# ADS1298_V1.net
KiCad netlist of a schematic drawn in EAGLE
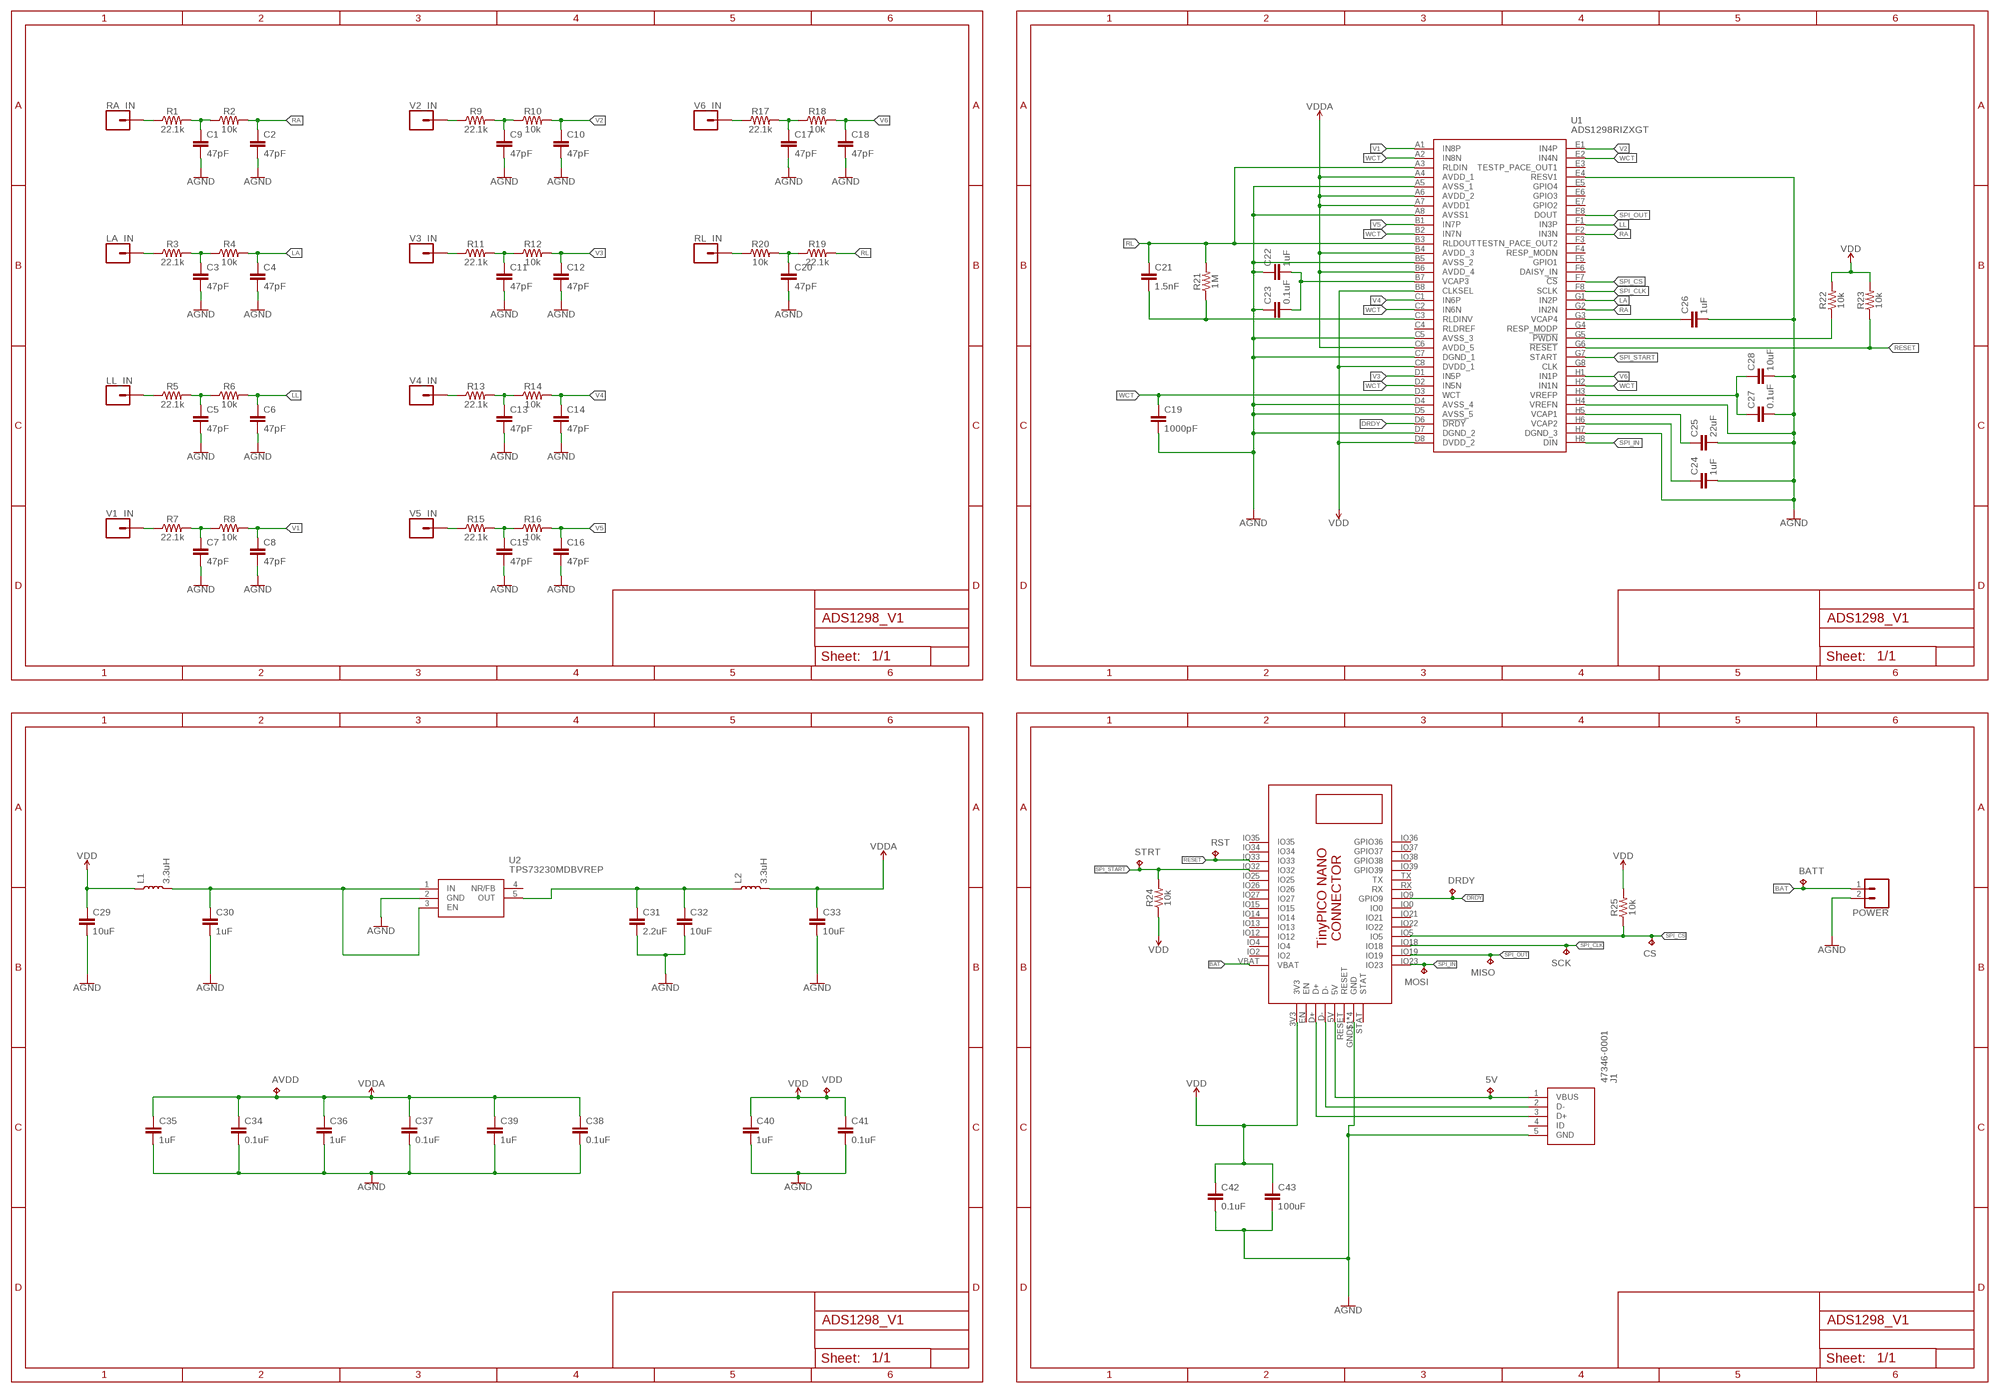
[diagram p0: schematic, sheet 1]

(export (version "E")
  (design (tool "Eeschema 10.0.6"))
  (components
    (comp (ref "5V")
      (value "TPB1,27")
      (footprint "eagle-import:B1,27")
      (libsource (lib "eagle-import") (part "TPB1,27"))
    )
    (comp (ref "AVDD")
      (value "TPB1,27")
      (footprint "eagle-import:B1,27")
      (libsource (lib "eagle-import") (part "TPB1,27"))
    )
    (comp (ref "BATT")
      (value "TPB1,27")
      (footprint "eagle-import:B1,27")
      (libsource (lib "eagle-import") (part "TPB1,27"))
    )
    (comp (ref "C1")
      (value "47pF")
      (footprint "eagle-import:0603")
      (libsource (lib "eagle-import") (part "CAP-0603"))
    )
    (comp (ref "C2")
      (value "47pF")
      (footprint "eagle-import:0603")
      (libsource (lib "eagle-import") (part "CAP-0603"))
    )
    (comp (ref "C3")
      (value "47pF")
      (footprint "eagle-import:0603")
      (libsource (lib "eagle-import") (part "CAP-0603"))
    )
    (comp (ref "C4")
      (value "47pF")
      (footprint "eagle-import:0603")
      (libsource (lib "eagle-import") (part "CAP-0603"))
    )
    (comp (ref "C5")
      (value "47pF")
      (footprint "eagle-import:0603")
      (libsource (lib "eagle-import") (part "CAP-0603"))
    )
    (comp (ref "C6")
      (value "47pF")
      (footprint "eagle-import:0603")
      (libsource (lib "eagle-import") (part "CAP-0603"))
    )
    (comp (ref "C7")
      (value "47pF")
      (footprint "eagle-import:0603")
      (libsource (lib "eagle-import") (part "CAP-0603"))
    )
    (comp (ref "C8")
      (value "47pF")
      (footprint "eagle-import:0603")
      (libsource (lib "eagle-import") (part "CAP-0603"))
    )
    (comp (ref "C9")
      (value "47pF")
      (footprint "eagle-import:0603")
      (libsource (lib "eagle-import") (part "CAP-0603"))
    )
    (comp (ref "C10")
      (value "47pF")
      (footprint "eagle-import:0603")
      (libsource (lib "eagle-import") (part "CAP-0603"))
    )
    (comp (ref "C11")
      (value "47pF")
      (footprint "eagle-import:0603")
      (libsource (lib "eagle-import") (part "CAP-0603"))
    )
    (comp (ref "C12")
      (value "47pF")
      (footprint "eagle-import:0603")
      (libsource (lib "eagle-import") (part "CAP-0603"))
    )
    (comp (ref "C13")
      (value "47pF")
      (footprint "eagle-import:0603")
      (libsource (lib "eagle-import") (part "CAP-0603"))
    )
    (comp (ref "C14")
      (value "47pF")
      (footprint "eagle-import:0603")
      (libsource (lib "eagle-import") (part "CAP-0603"))
    )
    (comp (ref "C15")
      (value "47pF")
      (footprint "eagle-import:0603")
      (libsource (lib "eagle-import") (part "CAP-0603"))
    )
    (comp (ref "C16")
      (value "47pF")
      (footprint "eagle-import:0603")
      (libsource (lib "eagle-import") (part "CAP-0603"))
    )
    (comp (ref "C17")
      (value "47pF")
      (footprint "eagle-import:0603")
      (libsource (lib "eagle-import") (part "CAP-0603"))
    )
    (comp (ref "C18")
      (value "47pF")
      (footprint "eagle-import:0603")
      (libsource (lib "eagle-import") (part "CAP-0603"))
    )
    (comp (ref "C19")
      (value "1000pF")
      (footprint "eagle-import:0603")
      (libsource (lib "eagle-import") (part "CAP-0603"))
    )
    (comp (ref "C20")
      (value "47pF")
      (footprint "eagle-import:0603")
      (libsource (lib "eagle-import") (part "CAP-0603"))
    )
    (comp (ref "C21")
      (value "1.5nF")
      (footprint "eagle-import:0603")
      (libsource (lib "eagle-import") (part "CAP-0603"))
    )
    (comp (ref "C22")
      (value "1uF")
      (footprint "eagle-import:0603")
      (libsource (lib "eagle-import") (part "CAP-0603"))
    )
    (comp (ref "C23")
      (value "0.1uF")
      (footprint "eagle-import:0603")
      (libsource (lib "eagle-import") (part "CAP-0603"))
    )
    (comp (ref "C24")
      (value "1uF")
      (footprint "eagle-import:0603")
      (libsource (lib "eagle-import") (part "CAP-0603"))
    )
    (comp (ref "C25")
      (value "22uF")
      (footprint "eagle-import:0805")
      (libsource (lib "eagle-import") (part "CAP-0805"))
    )
    (comp (ref "C26")
      (value "1uF")
      (footprint "eagle-import:0603")
      (libsource (lib "eagle-import") (part "CAP-0603"))
    )
    (comp (ref "C27")
      (value "0.1uF")
      (footprint "eagle-import:0603")
      (libsource (lib "eagle-import") (part "CAP-0603"))
    )
    (comp (ref "C28")
      (value "10uF")
      (footprint "eagle-import:0805")
      (libsource (lib "eagle-import") (part "CAP-0805"))
    )
    (comp (ref "C29")
      (value "10uF")
      (footprint "eagle-import:0805")
      (libsource (lib "eagle-import") (part "CAP-0805"))
    )
    (comp (ref "C30")
      (value "1uF")
      (footprint "eagle-import:0603")
      (libsource (lib "eagle-import") (part "CAP-0603"))
    )
    (comp (ref "C31")
      (value "2.2uF")
      (footprint "eagle-import:0603")
      (libsource (lib "eagle-import") (part "CAP-0603"))
    )
    (comp (ref "C32")
      (value "10uF")
      (footprint "eagle-import:0805")
      (libsource (lib "eagle-import") (part "CAP-0805"))
    )
    (comp (ref "C33")
      (value "10uF")
      (footprint "eagle-import:0805")
      (libsource (lib "eagle-import") (part "CAP-0805"))
    )
    (comp (ref "C34")
      (value "0.1uF")
      (footprint "eagle-import:0603")
      (libsource (lib "eagle-import") (part "CAP-0603"))
    )
    (comp (ref "C35")
      (value "1uF")
      (footprint "eagle-import:0603")
      (libsource (lib "eagle-import") (part "CAP-0603"))
    )
    (comp (ref "C36")
      (value "1uF")
      (footprint "eagle-import:0603")
      (libsource (lib "eagle-import") (part "CAP-0603"))
    )
    (comp (ref "C37")
      (value "0.1uF")
      (footprint "eagle-import:0603")
      (libsource (lib "eagle-import") (part "CAP-0603"))
    )
    (comp (ref "C38")
      (value "0.1uF")
      (footprint "eagle-import:0603")
      (libsource (lib "eagle-import") (part "CAP-0603"))
    )
    (comp (ref "C39")
      (value "1uF")
      (footprint "eagle-import:0603")
      (libsource (lib "eagle-import") (part "CAP-0603"))
    )
    (comp (ref "C40")
      (value "1uF")
      (footprint "eagle-import:0603")
      (libsource (lib "eagle-import") (part "CAP-0603"))
    )
    (comp (ref "C41")
      (value "0.1uF")
      (footprint "eagle-import:0603")
      (libsource (lib "eagle-import") (part "CAP-0603"))
    )
    (comp (ref "C42")
      (value "0.1uF")
      (footprint "eagle-import:0603")
      (libsource (lib "eagle-import") (part "CAP-0603"))
    )
    (comp (ref "C43")
      (value "100uF")
      (footprint "eagle-import:0805")
      (libsource (lib "eagle-import") (part "CAP-0805"))
    )
    (comp (ref "CS")
      (value "TPB1,27")
      (footprint "eagle-import:B1,27")
      (libsource (lib "eagle-import") (part "TPB1,27"))
    )
    (comp (ref "DRDY")
      (value "TPB1,27")
      (footprint "eagle-import:B1,27")
      (libsource (lib "eagle-import") (part "TPB1,27"))
    )
    (comp (ref "J1")
      (value "47346-0001")
      (footprint "eagle-import:47346-0001")
      (fields (field (name "MOUSER_PART_NUMBER") "538-47346-0001"))
      (libsource (lib "eagle-import") (part "47346-0001"))
    )
    (comp (ref "L1")
      (value "3.3uH")
      (footprint "eagle-import:0805")
      (libsource (lib "eagle-import") (part "INDUCTOR-0805-3.3UH"))
    )
    (comp (ref "L2")
      (value "3.3uH")
      (footprint "eagle-import:0805")
      (libsource (lib "eagle-import") (part "INDUCTOR-0805-3.3UH"))
    )
    (comp (ref "LA_IN")
      (value "CONN_01")
      (footprint "eagle-import:1X01")
      (libsource (lib "eagle-import") (part "CONN_01"))
    )
    (comp (ref "LL_IN")
      (value "CONN_01")
      (footprint "eagle-import:1X01")
      (libsource (lib "eagle-import") (part "CONN_01"))
    )
    (comp (ref "MISO")
      (value "TPB1,27")
      (footprint "eagle-import:B1,27")
      (libsource (lib "eagle-import") (part "TPB1,27"))
    )
    (comp (ref "MOSI")
      (value "TPB1,27")
      (footprint "eagle-import:B1,27")
      (libsource (lib "eagle-import") (part "TPB1,27"))
    )
    (comp (ref "POWER")
      (value "CONN_02")
      (footprint "eagle-import:1X02")
      (libsource (lib "eagle-import") (part "CONN_02"))
    )
    (comp (ref "R1")
      (value "22.1k")
      (footprint "eagle-import:0603")
      (libsource (lib "eagle-import") (part "RESISTOR0603"))
    )
    (comp (ref "R2")
      (value "10k")
      (footprint "eagle-import:0603")
      (libsource (lib "eagle-import") (part "RESISTOR0603"))
    )
    (comp (ref "R3")
      (value "22.1k")
      (footprint "eagle-import:0603")
      (libsource (lib "eagle-import") (part "RESISTOR0603"))
    )
    (comp (ref "R4")
      (value "10k")
      (footprint "eagle-import:0603")
      (libsource (lib "eagle-import") (part "RESISTOR0603"))
    )
    (comp (ref "R5")
      (value "22.1k")
      (footprint "eagle-import:0603")
      (libsource (lib "eagle-import") (part "RESISTOR0603"))
    )
    (comp (ref "R6")
      (value "10k")
      (footprint "eagle-import:0603")
      (libsource (lib "eagle-import") (part "RESISTOR0603"))
    )
    (comp (ref "R7")
      (value "22.1k")
      (footprint "eagle-import:0603")
      (libsource (lib "eagle-import") (part "RESISTOR0603"))
    )
    (comp (ref "R8")
      (value "10k")
      (footprint "eagle-import:0603")
      (libsource (lib "eagle-import") (part "RESISTOR0603"))
    )
    (comp (ref "R9")
      (value "22.1k")
      (footprint "eagle-import:0603")
      (libsource (lib "eagle-import") (part "RESISTOR0603"))
    )
    (comp (ref "R10")
      (value "10k")
      (footprint "eagle-import:0603")
      (libsource (lib "eagle-import") (part "RESISTOR0603"))
    )
    (comp (ref "R11")
      (value "22.1k")
      (footprint "eagle-import:0603")
      (libsource (lib "eagle-import") (part "RESISTOR0603"))
    )
    (comp (ref "R12")
      (value "10k")
      (footprint "eagle-import:0603")
      (libsource (lib "eagle-import") (part "RESISTOR0603"))
    )
    (comp (ref "R13")
      (value "22.1k")
      (footprint "eagle-import:0603")
      (libsource (lib "eagle-import") (part "RESISTOR0603"))
    )
    (comp (ref "R14")
      (value "10k")
      (footprint "eagle-import:0603")
      (libsource (lib "eagle-import") (part "RESISTOR0603"))
    )
    (comp (ref "R15")
      (value "22.1k")
      (footprint "eagle-import:0603")
      (libsource (lib "eagle-import") (part "RESISTOR0603"))
    )
    (comp (ref "R16")
      (value "10k")
      (footprint "eagle-import:0603")
      (libsource (lib "eagle-import") (part "RESISTOR0603"))
    )
    (comp (ref "R17")
      (value "22.1k")
      (footprint "eagle-import:0603")
      (libsource (lib "eagle-import") (part "RESISTOR0603"))
    )
    (comp (ref "R18")
      (value "10k")
      (footprint "eagle-import:0603")
      (libsource (lib "eagle-import") (part "RESISTOR0603"))
    )
    (comp (ref "R19")
      (value "22.1k")
      (footprint "eagle-import:0603")
      (libsource (lib "eagle-import") (part "RESISTOR0603"))
    )
    (comp (ref "R20")
      (value "10k")
      (footprint "eagle-import:0603")
      (libsource (lib "eagle-import") (part "RESISTOR0603"))
    )
    (comp (ref "R21")
      (value "1M")
      (footprint "eagle-import:0603")
      (libsource (lib "eagle-import") (part "RESISTOR0603"))
    )
    (comp (ref "R22")
      (value "10k")
      (footprint "eagle-import:0603")
      (libsource (lib "eagle-import") (part "RESISTOR0603"))
    )
    (comp (ref "R23")
      (value "10k")
      (footprint "eagle-import:0603")
      (libsource (lib "eagle-import") (part "RESISTOR0603"))
    )
    (comp (ref "R24")
      (value "10k")
      (footprint "eagle-import:0603")
      (libsource (lib "eagle-import") (part "RESISTOR0603"))
    )
    (comp (ref "R25")
      (value "10k")
      (footprint "eagle-import:0603")
      (libsource (lib "eagle-import") (part "RESISTOR0603"))
    )
    (comp (ref "RA_IN")
      (value "CONN_01")
      (footprint "eagle-import:1X01")
      (libsource (lib "eagle-import") (part "CONN_01"))
    )
    (comp (ref "RL_IN")
      (value "CONN_01")
      (footprint "eagle-import:1X01")
      (libsource (lib "eagle-import") (part "CONN_01"))
    )
    (comp (ref "RST")
      (value "TPB1,27")
      (footprint "eagle-import:B1,27")
      (libsource (lib "eagle-import") (part "TPB1,27"))
    )
    (comp (ref "SCK")
      (value "TPB1,27")
      (footprint "eagle-import:B1,27")
      (libsource (lib "eagle-import") (part "TPB1,27"))
    )
    (comp (ref "STRT")
      (value "TPB1,27")
      (footprint "eagle-import:B1,27")
      (libsource (lib "eagle-import") (part "TPB1,27"))
    )
    (comp (ref "U1")
      (value "ADS1298RIZXGT")
      (footprint "eagle-import:BGA64C80P8X8_800X800X145")
      (fields (field (name "MOUSER_PART_NUMBER") "595-ADS1298RIZXGT"))
      (libsource (lib "eagle-import") (part "ADS1298RIZXGT"))
    )
    (comp (ref "U2")
      (value "TPS73230MDBVREP")
      (footprint "eagle-import:SOT95P280X145-5N")
      (fields (field (name "MOUSER_PART_NUMBER") "595-TPS73230MDBVREP"))
      (libsource (lib "eagle-import") (part "TPS73230MDBVREP"))
    )
    (comp (ref "U3")
      (value "TINYPICO-NANO-CONNECTOR")
      (footprint "eagle-import:TINYPICO-NANO-CONNECTOR")
      (libsource (lib "eagle-import") (part "TINYPICO-NANO-CONNECTOR"))
    )
    (comp (ref "V1_IN")
      (value "CONN_01")
      (footprint "eagle-import:1X01")
      (libsource (lib "eagle-import") (part "CONN_01"))
    )
    (comp (ref "V2_IN")
      (value "CONN_01")
      (footprint "eagle-import:1X01")
      (libsource (lib "eagle-import") (part "CONN_01"))
    )
    (comp (ref "V3_IN")
      (value "CONN_01")
      (footprint "eagle-import:1X01")
      (libsource (lib "eagle-import") (part "CONN_01"))
    )
    (comp (ref "V4_IN")
      (value "CONN_01")
      (footprint "eagle-import:1X01")
      (libsource (lib "eagle-import") (part "CONN_01"))
    )
    (comp (ref "V5_IN")
      (value "CONN_01")
      (footprint "eagle-import:1X01")
      (libsource (lib "eagle-import") (part "CONN_01"))
    )
    (comp (ref "V6_IN")
      (value "CONN_01")
      (footprint "eagle-import:1X01")
      (libsource (lib "eagle-import") (part "CONN_01"))
    )
    (comp (ref "VDD")
      (value "TPB1,27")
      (footprint "eagle-import:B1,27")
      (libsource (lib "eagle-import") (part "TPB1,27"))
    )
  )
  (nets
    (net (code "1") (name "AGND") (class "Default")
      (node (ref "C1") (pin "2") (pinfunction "2_2") (pintype "passive"))
      (node (ref "C10") (pin "2") (pinfunction "2_2") (pintype "passive"))
      (node (ref "C11") (pin "2") (pinfunction "2_2") (pintype "passive"))
      (node (ref "C12") (pin "2") (pinfunction "2_2") (pintype "passive"))
      (node (ref "C13") (pin "2") (pinfunction "2_2") (pintype "passive"))
      (node (ref "C14") (pin "2") (pinfunction "2_2") (pintype "passive"))
      (node (ref "C15") (pin "2") (pinfunction "2_2") (pintype "passive"))
      (node (ref "C16") (pin "2") (pinfunction "2_2") (pintype "passive"))
      (node (ref "C17") (pin "2") (pinfunction "2_2") (pintype "passive"))
      (node (ref "C18") (pin "2") (pinfunction "2_2") (pintype "passive"))
      (node (ref "C19") (pin "2") (pinfunction "2_2") (pintype "passive"))
      (node (ref "C2") (pin "2") (pinfunction "2_2") (pintype "passive"))
      (node (ref "C20") (pin "2") (pinfunction "2_2") (pintype "passive"))
      (node (ref "C22") (pin "1") (pinfunction "1_1") (pintype "passive"))
      (node (ref "C23") (pin "1") (pinfunction "1_1") (pintype "passive"))
      (node (ref "C24") (pin "2") (pinfunction "2_2") (pintype "passive"))
      (node (ref "C25") (pin "2") (pinfunction "2_2") (pintype "passive"))
      (node (ref "C26") (pin "2") (pinfunction "2_2") (pintype "passive"))
      (node (ref "C27") (pin "2") (pinfunction "2_2") (pintype "passive"))
      (node (ref "C28") (pin "2") (pinfunction "2_2") (pintype "passive"))
      (node (ref "C29") (pin "2") (pinfunction "2_2") (pintype "passive"))
      (node (ref "C3") (pin "2") (pinfunction "2_2") (pintype "passive"))
      (node (ref "C30") (pin "2") (pinfunction "2_2") (pintype "passive"))
      (node (ref "C31") (pin "2") (pinfunction "2_2") (pintype "passive"))
      (node (ref "C32") (pin "2") (pinfunction "2_2") (pintype "passive"))
      (node (ref "C33") (pin "2") (pinfunction "2_2") (pintype "passive"))
      (node (ref "C34") (pin "2") (pinfunction "2_2") (pintype "passive"))
      (node (ref "C35") (pin "2") (pinfunction "2_2") (pintype "passive"))
      (node (ref "C36") (pin "2") (pinfunction "2_2") (pintype "passive"))
      (node (ref "C37") (pin "2") (pinfunction "2_2") (pintype "passive"))
      (node (ref "C38") (pin "2") (pinfunction "2_2") (pintype "passive"))
      (node (ref "C39") (pin "2") (pinfunction "2_2") (pintype "passive"))
      (node (ref "C4") (pin "2") (pinfunction "2_2") (pintype "passive"))
      (node (ref "C40") (pin "2") (pinfunction "2_2") (pintype "passive"))
      (node (ref "C41") (pin "2") (pinfunction "2_2") (pintype "passive"))
      (node (ref "C42") (pin "2") (pinfunction "2_2") (pintype "passive"))
      (node (ref "C43") (pin "2") (pinfunction "2_2") (pintype "passive"))
      (node (ref "C5") (pin "2") (pinfunction "2_2") (pintype "passive"))
      (node (ref "C6") (pin "2") (pinfunction "2_2") (pintype "passive"))
      (node (ref "C7") (pin "2") (pinfunction "2_2") (pintype "passive"))
      (node (ref "C8") (pin "2") (pinfunction "2_2") (pintype "passive"))
      (node (ref "C9") (pin "2") (pinfunction "2_2") (pintype "passive"))
      (node (ref "J1") (pin "5") (pinfunction "GND_5") (pintype "bidirectional"))
      (node (ref "POWER") (pin "2") (pinfunction "2_2") (pintype "passive"))
      (node (ref "U1") (pin "A5") (pinfunction "AVSS_1_A5") (pintype "bidirectional"))
      (node (ref "U1") (pin "A8") (pinfunction "AVSS1_A8") (pintype "bidirectional"))
      (node (ref "U1") (pin "B5") (pinfunction "AVSS_2_B5") (pintype "bidirectional"))
      (node (ref "U1") (pin "C5") (pinfunction "AVSS_3_C5") (pintype "bidirectional"))
      (node (ref "U1") (pin "C7") (pinfunction "DGND_1_C7") (pintype "bidirectional"))
      (node (ref "U1") (pin "D4") (pinfunction "AVSS_4_D4") (pintype "bidirectional"))
      (node (ref "U1") (pin "D5") (pinfunction "AVSS_5_D5") (pintype "bidirectional"))
      (node (ref "U1") (pin "D7") (pinfunction "DGND_2_D7") (pintype "bidirectional"))
      (node (ref "U1") (pin "E4") (pinfunction "RESV1_E4") (pintype "bidirectional"))
      (node (ref "U1") (pin "H4") (pinfunction "VREFN_H4") (pintype "bidirectional"))
      (node (ref "U1") (pin "H7") (pinfunction "DGND_3_H7") (pintype "bidirectional"))
      (node (ref "U2") (pin "2") (pinfunction "GND_2") (pintype "bidirectional"))
      (node (ref "U3") (pin "GND$1") (pinfunction "GND_GND$1") (pintype "power_in"))
      (node (ref "U3") (pin "GND$2") (pinfunction "GND_GND$2") (pintype "power_in"))
      (node (ref "U3") (pin "GND$3") (pinfunction "GND_GND$3") (pintype "power_in"))
      (node (ref "U3") (pin "GND$4") (pinfunction "GND_GND$4") (pintype "power_in"))
    )
    (net (code "2") (name "BAT") (class "Default")
      (node (ref "BATT") (pin "TP") (pinfunction "TP_TP") (pintype "input"))
      (node (ref "POWER") (pin "1") (pinfunction "1_1") (pintype "passive"))
      (node (ref "U3") (pin "VBAT") (pinfunction "VBAT_VBAT") (pintype "power_in"))
    )
    (net (code "3") (name "DRDY") (class "Default")
      (node (ref "DRDY") (pin "TP") (pinfunction "TP_TP") (pintype "input"))
      (node (ref "U1") (pin "D6") (pinfunction "~{DRDY}_D6") (pintype "bidirectional"))
      (node (ref "U3") (pin "IO9") (pinfunction "GPIO9_IO9") (pintype "bidirectional"))
    )
    (net (code "4") (name "LA") (class "Default")
      (node (ref "C4") (pin "1") (pinfunction "1_1") (pintype "passive"))
      (node (ref "R4") (pin "2") (pinfunction "2_2") (pintype "passive"))
      (node (ref "U1") (pin "G1") (pinfunction "IN2P_G1") (pintype "bidirectional"))
    )
    (net (code "5") (name "LL") (class "Default")
      (node (ref "C6") (pin "1") (pinfunction "1_1") (pintype "passive"))
      (node (ref "R6") (pin "2") (pinfunction "2_2") (pintype "passive"))
      (node (ref "U1") (pin "F1") (pinfunction "IN3P_F1") (pintype "bidirectional"))
    )
    (net (code "6") (name "Net-(C1-Pad1)") (class "Default")
      (node (ref "C1") (pin "1") (pinfunction "1_1") (pintype "passive"))
      (node (ref "R1") (pin "2") (pinfunction "2_2") (pintype "passive"))
      (node (ref "R2") (pin "1") (pinfunction "1_1") (pintype "passive"))
    )
    (net (code "7") (name "Net-(C3-Pad1)") (class "Default")
      (node (ref "C3") (pin "1") (pinfunction "1_1") (pintype "passive"))
      (node (ref "R3") (pin "2") (pinfunction "2_2") (pintype "passive"))
      (node (ref "R4") (pin "1") (pinfunction "1_1") (pintype "passive"))
    )
    (net (code "8") (name "Net-(C5-Pad1)") (class "Default")
      (node (ref "C5") (pin "1") (pinfunction "1_1") (pintype "passive"))
      (node (ref "R5") (pin "2") (pinfunction "2_2") (pintype "passive"))
      (node (ref "R6") (pin "1") (pinfunction "1_1") (pintype "passive"))
    )
    (net (code "9") (name "Net-(C7-Pad1)") (class "Default")
      (node (ref "C7") (pin "1") (pinfunction "1_1") (pintype "passive"))
      (node (ref "R7") (pin "2") (pinfunction "2_2") (pintype "passive"))
      (node (ref "R8") (pin "1") (pinfunction "1_1") (pintype "passive"))
    )
    (net (code "10") (name "Net-(C9-Pad1)") (class "Default")
      (node (ref "C9") (pin "1") (pinfunction "1_1") (pintype "passive"))
      (node (ref "R10") (pin "1") (pinfunction "1_1") (pintype "passive"))
      (node (ref "R9") (pin "2") (pinfunction "2_2") (pintype "passive"))
    )
    (net (code "11") (name "Net-(C11-Pad1)") (class "Default")
      (node (ref "C11") (pin "1") (pinfunction "1_1") (pintype "passive"))
      (node (ref "R11") (pin "2") (pinfunction "2_2") (pintype "passive"))
      (node (ref "R12") (pin "1") (pinfunction "1_1") (pintype "passive"))
    )
    (net (code "12") (name "Net-(C13-Pad1)") (class "Default")
      (node (ref "C13") (pin "1") (pinfunction "1_1") (pintype "passive"))
      (node (ref "R13") (pin "2") (pinfunction "2_2") (pintype "passive"))
      (node (ref "R14") (pin "1") (pinfunction "1_1") (pintype "passive"))
    )
    (net (code "13") (name "Net-(C15-Pad1)") (class "Default")
      (node (ref "C15") (pin "1") (pinfunction "1_1") (pintype "passive"))
      (node (ref "R15") (pin "2") (pinfunction "2_2") (pintype "passive"))
      (node (ref "R16") (pin "1") (pinfunction "1_1") (pintype "passive"))
    )
    (net (code "14") (name "Net-(C17-Pad1)") (class "Default")
      (node (ref "C17") (pin "1") (pinfunction "1_1") (pintype "passive"))
      (node (ref "R17") (pin "2") (pinfunction "2_2") (pintype "passive"))
      (node (ref "R18") (pin "1") (pinfunction "1_1") (pintype "passive"))
    )
    (net (code "15") (name "Net-(C20-Pad1)") (class "Default")
      (node (ref "C20") (pin "1") (pinfunction "1_1") (pintype "passive"))
      (node (ref "R19") (pin "1") (pinfunction "1_1") (pintype "passive"))
      (node (ref "R20") (pin "2") (pinfunction "2_2") (pintype "passive"))
    )
    (net (code "16") (name "Net-(J1-D+)") (class "Default")
      (node (ref "J1") (pin "3") (pinfunction "D+_3") (pintype "bidirectional"))
      (node (ref "U3") (pin "D+") (pinfunction "D+_D+") (pintype "bidirectional"))
    )
    (net (code "17") (name "Net-(J1-D-)") (class "Default")
      (node (ref "J1") (pin "2") (pinfunction "D-_2") (pintype "bidirectional"))
      (node (ref "U3") (pin "D-") (pinfunction "D-_D-") (pintype "bidirectional"))
    )
    (net (code "18") (name "Net-(J1-VBUS)") (class "Default")
      (node (ref "5V") (pin "TP") (pinfunction "TP_TP") (pintype "input"))
      (node (ref "J1") (pin "1") (pinfunction "VBUS_1") (pintype "bidirectional"))
      (node (ref "U3") (pin "5V") (pinfunction "5V_5V") (pintype "power_in"))
    )
    (net (code "19") (name "Net-(LA_IN-Pad1)") (class "Default")
      (node (ref "LA_IN") (pin "1") (pinfunction "1_1") (pintype "passive"))
      (node (ref "R3") (pin "1") (pinfunction "1_1") (pintype "passive"))
    )
    (net (code "20") (name "Net-(LL_IN-Pad1)") (class "Default")
      (node (ref "LL_IN") (pin "1") (pinfunction "1_1") (pintype "passive"))
      (node (ref "R5") (pin "1") (pinfunction "1_1") (pintype "passive"))
    )
    (net (code "21") (name "Net-(R1-Pad1)") (class "Default")
      (node (ref "R1") (pin "1") (pinfunction "1_1") (pintype "passive"))
      (node (ref "RA_IN") (pin "1") (pinfunction "1_1") (pintype "passive"))
    )
    (net (code "22") (name "Net-(R7-Pad1)") (class "Default")
      (node (ref "R7") (pin "1") (pinfunction "1_1") (pintype "passive"))
      (node (ref "V1_IN") (pin "1") (pinfunction "1_1") (pintype "passive"))
    )
    (net (code "23") (name "Net-(R9-Pad1)") (class "Default")
      (node (ref "R9") (pin "1") (pinfunction "1_1") (pintype "passive"))
      (node (ref "V2_IN") (pin "1") (pinfunction "1_1") (pintype "passive"))
    )
    (net (code "24") (name "Net-(R11-Pad1)") (class "Default")
      (node (ref "R11") (pin "1") (pinfunction "1_1") (pintype "passive"))
      (node (ref "V3_IN") (pin "1") (pinfunction "1_1") (pintype "passive"))
    )
    (net (code "25") (name "Net-(R13-Pad1)") (class "Default")
      (node (ref "R13") (pin "1") (pinfunction "1_1") (pintype "passive"))
      (node (ref "V4_IN") (pin "1") (pinfunction "1_1") (pintype "passive"))
    )
    (net (code "26") (name "Net-(R15-Pad1)") (class "Default")
      (node (ref "R15") (pin "1") (pinfunction "1_1") (pintype "passive"))
      (node (ref "V5_IN") (pin "1") (pinfunction "1_1") (pintype "passive"))
    )
    (net (code "27") (name "Net-(R17-Pad1)") (class "Default")
      (node (ref "R17") (pin "1") (pinfunction "1_1") (pintype "passive"))
      (node (ref "V6_IN") (pin "1") (pinfunction "1_1") (pintype "passive"))
    )
    (net (code "28") (name "Net-(R20-Pad1)") (class "Default")
      (node (ref "R20") (pin "1") (pinfunction "1_1") (pintype "passive"))
      (node (ref "RL_IN") (pin "1") (pinfunction "1_1") (pintype "passive"))
    )
    (net (code "29") (name "Net-(U1-RLDINV)") (class "Default")
      (node (ref "C21") (pin "2") (pinfunction "2_2") (pintype "passive"))
      (node (ref "R21") (pin "1") (pinfunction "1_1") (pintype "passive"))
      (node (ref "U1") (pin "C3") (pinfunction "RLDINV_C3") (pintype "bidirectional"))
    )
    (net (code "30") (name "Net-(U1-VCAP1)") (class "Default")
      (node (ref "C25") (pin "1") (pinfunction "1_1") (pintype "passive"))
      (node (ref "U1") (pin "H5") (pinfunction "VCAP1_H5") (pintype "bidirectional"))
    )
    (net (code "31") (name "Net-(U1-VCAP2)") (class "Default")
      (node (ref "C24") (pin "1") (pinfunction "1_1") (pintype "passive"))
      (node (ref "U1") (pin "H6") (pinfunction "VCAP2_H6") (pintype "bidirectional"))
    )
    (net (code "32") (name "Net-(U1-VCAP3)") (class "Default")
      (node (ref "C22") (pin "2") (pinfunction "2_2") (pintype "passive"))
      (node (ref "C23") (pin "2") (pinfunction "2_2") (pintype "passive"))
      (node (ref "U1") (pin "B7") (pinfunction "VCAP3_B7") (pintype "bidirectional"))
    )
    (net (code "33") (name "Net-(U1-VCAP4)") (class "Default")
      (node (ref "C26") (pin "1") (pinfunction "1_1") (pintype "passive"))
      (node (ref "U1") (pin "G3") (pinfunction "VCAP4_G3") (pintype "bidirectional"))
    )
    (net (code "34") (name "Net-(U1-VREFP)") (class "Default")
      (node (ref "C27") (pin "1") (pinfunction "1_1") (pintype "passive"))
      (node (ref "C28") (pin "1") (pinfunction "1_1") (pintype "passive"))
      (node (ref "U1") (pin "H3") (pinfunction "VREFP_H3") (pintype "bidirectional"))
    )
    (net (code "35") (name "Net-(U1-~{PWDN})") (class "Default")
      (node (ref "R22") (pin "1") (pinfunction "1_1") (pintype "passive"))
      (node (ref "U1") (pin "G5") (pinfunction "~{PWDN}_G5") (pintype "bidirectional"))
    )
    (net (code "36") (name "Net-(U2-EN)") (class "Default")
      (node (ref "C30") (pin "1") (pinfunction "1_1") (pintype "passive"))
      (node (ref "L1") (pin "2") (pinfunction "2_2") (pintype "passive"))
      (node (ref "U2") (pin "1") (pinfunction "IN_1") (pintype "bidirectional"))
      (node (ref "U2") (pin "3") (pinfunction "EN_3") (pintype "bidirectional"))
    )
    (net (code "37") (name "Net-(U2-OUT)") (class "Default")
      (node (ref "C31") (pin "1") (pinfunction "1_1") (pintype "passive"))
      (node (ref "C32") (pin "1") (pinfunction "1_1") (pintype "passive"))
      (node (ref "L2") (pin "1") (pinfunction "1_1") (pintype "passive"))
      (node (ref "U2") (pin "5") (pinfunction "OUT_5") (pintype "bidirectional"))
    )
    (net (code "38") (name "RA") (class "Default")
      (node (ref "C2") (pin "1") (pinfunction "1_1") (pintype "passive"))
      (node (ref "R2") (pin "2") (pinfunction "2_2") (pintype "passive"))
      (node (ref "U1") (pin "F2") (pinfunction "IN3N_F2") (pintype "bidirectional"))
      (node (ref "U1") (pin "G2") (pinfunction "IN2N_G2") (pintype "bidirectional"))
    )
    (net (code "39") (name "RESET") (class "Default")
      (node (ref "R23") (pin "1") (pinfunction "1_1") (pintype "passive"))
      (node (ref "RST") (pin "TP") (pinfunction "TP_TP") (pintype "input"))
      (node (ref "U1") (pin "G6") (pinfunction "~{RESET}_G6") (pintype "bidirectional"))
      (node (ref "U3") (pin "IO33") (pinfunction "IO33_IO33") (pintype "bidirectional"))
    )
    (net (code "40") (name "RL") (class "Default")
      (node (ref "C21") (pin "1") (pinfunction "1_1") (pintype "passive"))
      (node (ref "R19") (pin "2") (pinfunction "2_2") (pintype "passive"))
      (node (ref "R21") (pin "2") (pinfunction "2_2") (pintype "passive"))
      (node (ref "U1") (pin "A3") (pinfunction "RLDIN_A3") (pintype "bidirectional"))
      (node (ref "U1") (pin "B3") (pinfunction "RLDOUT_B3") (pintype "bidirectional"))
    )
    (net (code "41") (name "SPI_CLK") (class "Default")
      (node (ref "SCK") (pin "TP") (pinfunction "TP_TP") (pintype "input"))
      (node (ref "U1") (pin "F8") (pinfunction "SCLK_F8") (pintype "bidirectional"))
      (node (ref "U3") (pin "IO18") (pinfunction "IO18_IO18") (pintype "bidirectional"))
    )
    (net (code "42") (name "SPI_CS") (class "Default")
      (node (ref "CS") (pin "TP") (pinfunction "TP_TP") (pintype "input"))
      (node (ref "R25") (pin "1") (pinfunction "1_1") (pintype "passive"))
      (node (ref "U1") (pin "F7") (pinfunction "~{CS}_F7") (pintype "bidirectional"))
      (node (ref "U3") (pin "IO5") (pinfunction "IO5_IO5") (pintype "bidirectional"))
    )
    (net (code "43") (name "SPI_IN") (class "Default")
      (node (ref "MOSI") (pin "TP") (pinfunction "TP_TP") (pintype "input"))
      (node (ref "U1") (pin "H8") (pinfunction "DIN_H8") (pintype "bidirectional"))
      (node (ref "U3") (pin "IO23") (pinfunction "IO23_IO23") (pintype "bidirectional"))
    )
    (net (code "44") (name "SPI_OUT") (class "Default")
      (node (ref "MISO") (pin "TP") (pinfunction "TP_TP") (pintype "input"))
      (node (ref "U1") (pin "E8") (pinfunction "DOUT_E8") (pintype "bidirectional"))
      (node (ref "U3") (pin "IO19") (pinfunction "IO19_IO19") (pintype "bidirectional"))
    )
    (net (code "45") (name "SPI_START") (class "Default")
      (node (ref "R24") (pin "2") (pinfunction "2_2") (pintype "passive"))
      (node (ref "STRT") (pin "TP") (pinfunction "TP_TP") (pintype "input"))
      (node (ref "U1") (pin "G7") (pinfunction "START_G7") (pintype "bidirectional"))
      (node (ref "U3") (pin "IO32") (pinfunction "IO32_IO32") (pintype "bidirectional"))
    )
    (net (code "46") (name "V1") (class "Default")
      (node (ref "C8") (pin "1") (pinfunction "1_1") (pintype "passive"))
      (node (ref "R8") (pin "2") (pinfunction "2_2") (pintype "passive"))
      (node (ref "U1") (pin "A1") (pinfunction "IN8P_A1") (pintype "bidirectional"))
    )
    (net (code "47") (name "V2") (class "Default")
      (node (ref "C10") (pin "1") (pinfunction "1_1") (pintype "passive"))
      (node (ref "R10") (pin "2") (pinfunction "2_2") (pintype "passive"))
      (node (ref "U1") (pin "E1") (pinfunction "IN4P_E1") (pintype "bidirectional"))
    )
    (net (code "48") (name "V3") (class "Default")
      (node (ref "C12") (pin "1") (pinfunction "1_1") (pintype "passive"))
      (node (ref "R12") (pin "2") (pinfunction "2_2") (pintype "passive"))
      (node (ref "U1") (pin "D1") (pinfunction "IN5P_D1") (pintype "bidirectional"))
    )
    (net (code "49") (name "V4") (class "Default")
      (node (ref "C14") (pin "1") (pinfunction "1_1") (pintype "passive"))
      (node (ref "R14") (pin "2") (pinfunction "2_2") (pintype "passive"))
      (node (ref "U1") (pin "C1") (pinfunction "IN6P_C1") (pintype "bidirectional"))
    )
    (net (code "50") (name "V5") (class "Default")
      (node (ref "C16") (pin "1") (pinfunction "1_1") (pintype "passive"))
      (node (ref "R16") (pin "2") (pinfunction "2_2") (pintype "passive"))
      (node (ref "U1") (pin "B1") (pinfunction "IN7P_B1") (pintype "bidirectional"))
    )
    (net (code "51") (name "V6") (class "Default")
      (node (ref "C18") (pin "1") (pinfunction "1_1") (pintype "passive"))
      (node (ref "R18") (pin "2") (pinfunction "2_2") (pintype "passive"))
      (node (ref "U1") (pin "H1") (pinfunction "IN1P_H1") (pintype "bidirectional"))
    )
    (net (code "52") (name "VDD") (class "Default")
      (node (ref "C29") (pin "1") (pinfunction "1_1") (pintype "passive"))
      (node (ref "C40") (pin "1") (pinfunction "1_1") (pintype "passive"))
      (node (ref "C41") (pin "1") (pinfunction "1_1") (pintype "passive"))
      (node (ref "C42") (pin "1") (pinfunction "1_1") (pintype "passive"))
      (node (ref "C43") (pin "1") (pinfunction "1_1") (pintype "passive"))
      (node (ref "L1") (pin "1") (pinfunction "1_1") (pintype "passive"))
      (node (ref "R22") (pin "2") (pinfunction "2_2") (pintype "passive"))
      (node (ref "R23") (pin "2") (pinfunction "2_2") (pintype "passive"))
      (node (ref "R24") (pin "1") (pinfunction "1_1") (pintype "passive"))
      (node (ref "R25") (pin "2") (pinfunction "2_2") (pintype "passive"))
      (node (ref "U1") (pin "B8") (pinfunction "CLKSEL_B8") (pintype "bidirectional"))
      (node (ref "U1") (pin "C8") (pinfunction "DVDD_1_C8") (pintype "bidirectional"))
      (node (ref "U1") (pin "D8") (pinfunction "DVDD_2_D8") (pintype "bidirectional"))
      (node (ref "U3") (pin "3V3") (pinfunction "3V3_3V3") (pintype "power_in"))
      (node (ref "VDD") (pin "TP") (pinfunction "TP_TP") (pintype "input"))
    )
    (net (code "53") (name "VDDA") (class "Default")
      (node (ref "AVDD") (pin "TP") (pinfunction "TP_TP") (pintype "input"))
      (node (ref "C33") (pin "1") (pinfunction "1_1") (pintype "passive"))
      (node (ref "C34") (pin "1") (pinfunction "1_1") (pintype "passive"))
      (node (ref "C35") (pin "1") (pinfunction "1_1") (pintype "passive"))
      (node (ref "C36") (pin "1") (pinfunction "1_1") (pintype "passive"))
      (node (ref "C37") (pin "1") (pinfunction "1_1") (pintype "passive"))
      (node (ref "C38") (pin "1") (pinfunction "1_1") (pintype "passive"))
      (node (ref "C39") (pin "1") (pinfunction "1_1") (pintype "passive"))
      (node (ref "L2") (pin "2") (pinfunction "2_2") (pintype "passive"))
      (node (ref "U1") (pin "A4") (pinfunction "AVDD_1_A4") (pintype "bidirectional"))
      (node (ref "U1") (pin "A6") (pinfunction "AVDD_2_A6") (pintype "bidirectional"))
      (node (ref "U1") (pin "A7") (pinfunction "AVDD1_A7") (pintype "bidirectional"))
      (node (ref "U1") (pin "B4") (pinfunction "AVDD_3_B4") (pintype "bidirectional"))
      (node (ref "U1") (pin "B6") (pinfunction "AVDD_4_B6") (pintype "bidirectional"))
      (node (ref "U1") (pin "C6") (pinfunction "AVDD_5_C6") (pintype "bidirectional"))
    )
    (net (code "54") (name "WCT") (class "Default")
      (node (ref "C19") (pin "1") (pinfunction "1_1") (pintype "passive"))
      (node (ref "U1") (pin "A2") (pinfunction "IN8N_A2") (pintype "bidirectional"))
      (node (ref "U1") (pin "B2") (pinfunction "IN7N_B2") (pintype "bidirectional"))
      (node (ref "U1") (pin "C2") (pinfunction "IN6N_C2") (pintype "bidirectional"))
      (node (ref "U1") (pin "D2") (pinfunction "IN5N_D2") (pintype "bidirectional"))
      (node (ref "U1") (pin "D3") (pinfunction "WCT_D3") (pintype "bidirectional"))
      (node (ref "U1") (pin "E2") (pinfunction "IN4N_E2") (pintype "bidirectional"))
      (node (ref "U1") (pin "H2") (pinfunction "IN1N_H2") (pintype "bidirectional"))
    )
    (net (code "55") (name "unconnected-(J1-ID-Pad4)") (class "Default")
      (node (ref "J1") (pin "4") (pinfunction "ID_4") (pintype "bidirectional"))
    )
    (net (code "56") (name "unconnected-(U1-CLK-PadG8)") (class "Default")
      (node (ref "U1") (pin "G8") (pinfunction "CLK_G8") (pintype "bidirectional"))
    )
    (net (code "57") (name "unconnected-(U1-DAISY_IN-PadF6)") (class "Default")
      (node (ref "U1") (pin "F6") (pinfunction "DAISY_IN_F6") (pintype "bidirectional"))
    )
    (net (code "58") (name "unconnected-(U1-GPIO1-PadF5)") (class "Default")
      (node (ref "U1") (pin "F5") (pinfunction "GPIO1_F5") (pintype "bidirectional"))
    )
    (net (code "59") (name "unconnected-(U1-GPIO2-PadE7)") (class "Default")
      (node (ref "U1") (pin "E7") (pinfunction "GPIO2_E7") (pintype "bidirectional"))
    )
    (net (code "60") (name "unconnected-(U1-GPIO3-PadE6)") (class "Default")
      (node (ref "U1") (pin "E6") (pinfunction "GPIO3_E6") (pintype "bidirectional"))
    )
    (net (code "61") (name "unconnected-(U1-GPIO4-PadE5)") (class "Default")
      (node (ref "U1") (pin "E5") (pinfunction "GPIO4_E5") (pintype "bidirectional"))
    )
    (net (code "62") (name "unconnected-(U1-RESP_MODN-PadF4)") (class "Default")
      (node (ref "U1") (pin "F4") (pinfunction "RESP_MODN_F4") (pintype "bidirectional"))
    )
    (net (code "63") (name "unconnected-(U1-RESP_MODP-PadG4)") (class "Default")
      (node (ref "U1") (pin "G4") (pinfunction "RESP_MODP_G4") (pintype "bidirectional"))
    )
    (net (code "64") (name "unconnected-(U1-RLDREF-PadC4)") (class "Default")
      (node (ref "U1") (pin "C4") (pinfunction "RLDREF_C4") (pintype "bidirectional"))
    )
    (net (code "65") (name "unconnected-(U1-TESTN_PACE_OUT2-PadF3)") (class "Default")
      (node (ref "U1") (pin "F3") (pinfunction "TESTN_PACE_OUT2_F3") (pintype "bidirectional"))
    )
    (net (code "66") (name "unconnected-(U1-TESTP_PACE_OUT1-PadE3)") (class "Default")
      (node (ref "U1") (pin "E3") (pinfunction "TESTP_PACE_OUT1_E3") (pintype "bidirectional"))
    )
    (net (code "67") (name "unconnected-(U2-NR{slash}FB-Pad4)") (class "Default")
      (node (ref "U2") (pin "4") (pinfunction "NR/FB_4") (pintype "bidirectional"))
    )
    (net (code "68") (name "unconnected-(U3-GPIO36-PadIO36)") (class "Default")
      (node (ref "U3") (pin "IO36") (pinfunction "GPIO36_IO36") (pintype "bidirectional"))
    )
    (net (code "69") (name "unconnected-(U3-GPIO37-PadIO37)") (class "Default")
      (node (ref "U3") (pin "IO37") (pinfunction "GPIO37_IO37") (pintype "bidirectional"))
    )
    (net (code "70") (name "unconnected-(U3-GPIO38-PadIO38)") (class "Default")
      (node (ref "U3") (pin "IO38") (pinfunction "GPIO38_IO38") (pintype "bidirectional"))
    )
    (net (code "71") (name "unconnected-(U3-GPIO39-PadIO39)") (class "Default")
      (node (ref "U3") (pin "IO39") (pinfunction "GPIO39_IO39") (pintype "bidirectional"))
    )
    (net (code "72") (name "unconnected-(U3-PadEN)") (class "Default")
      (node (ref "U3") (pin "EN") (pinfunction "EN_EN") (pintype "input"))
    )
    (net (code "73") (name "unconnected-(U3-PadIO0)") (class "Default")
      (node (ref "U3") (pin "IO0") (pinfunction "IO0_IO0") (pintype "bidirectional"))
    )
    (net (code "74") (name "unconnected-(U3-PadIO2)") (class "Default")
      (node (ref "U3") (pin "IO2") (pinfunction "IO2_IO2") (pintype "bidirectional"))
    )
    (net (code "75") (name "unconnected-(U3-PadIO4)") (class "Default")
      (node (ref "U3") (pin "IO4") (pinfunction "IO4_IO4") (pintype "bidirectional"))
    )
    (net (code "76") (name "unconnected-(U3-PadIO12)") (class "Default")
      (node (ref "U3") (pin "IO12") (pinfunction "IO12_IO12") (pintype "bidirectional"))
    )
    (net (code "77") (name "unconnected-(U3-PadIO13)") (class "Default")
      (node (ref "U3") (pin "IO13") (pinfunction "IO13_IO13") (pintype "bidirectional"))
    )
    (net (code "78") (name "unconnected-(U3-PadIO14)") (class "Default")
      (node (ref "U3") (pin "IO14") (pinfunction "IO14_IO14") (pintype "bidirectional"))
    )
    (net (code "79") (name "unconnected-(U3-PadIO15)") (class "Default")
      (node (ref "U3") (pin "IO15") (pinfunction "IO15_IO15") (pintype "bidirectional"))
    )
    (net (code "80") (name "unconnected-(U3-PadIO21)") (class "Default")
      (node (ref "U3") (pin "IO21") (pinfunction "IO21_IO21") (pintype "bidirectional"))
    )
    (net (code "81") (name "unconnected-(U3-PadIO22)") (class "Default")
      (node (ref "U3") (pin "IO22") (pinfunction "IO22_IO22") (pintype "bidirectional"))
    )
    (net (code "82") (name "unconnected-(U3-PadIO25)") (class "Default")
      (node (ref "U3") (pin "IO25") (pinfunction "IO25_IO25") (pintype "bidirectional"))
    )
    (net (code "83") (name "unconnected-(U3-PadIO26)") (class "Default")
      (node (ref "U3") (pin "IO26") (pinfunction "IO26_IO26") (pintype "bidirectional"))
    )
    (net (code "84") (name "unconnected-(U3-PadIO27)") (class "Default")
      (node (ref "U3") (pin "IO27") (pinfunction "IO27_IO27") (pintype "bidirectional"))
    )
    (net (code "85") (name "unconnected-(U3-PadIO34)") (class "Default")
      (node (ref "U3") (pin "IO34") (pinfunction "IO34_IO34") (pintype "bidirectional"))
    )
    (net (code "86") (name "unconnected-(U3-PadIO35)") (class "Default")
      (node (ref "U3") (pin "IO35") (pinfunction "IO35_IO35") (pintype "bidirectional"))
    )
    (net (code "87") (name "unconnected-(U3-PadRESET)") (class "Default")
      (node (ref "U3") (pin "RESET") (pinfunction "RESET_RESET") (pintype "bidirectional"))
    )
    (net (code "88") (name "unconnected-(U3-PadRX)") (class "Default")
      (node (ref "U3") (pin "RX") (pinfunction "RX_RX") (pintype "bidirectional"))
    )
    (net (code "89") (name "unconnected-(U3-PadSTAT)") (class "Default")
      (node (ref "U3") (pin "STAT") (pinfunction "STAT_STAT") (pintype "output"))
    )
    (net (code "90") (name "unconnected-(U3-PadTX)") (class "Default")
      (node (ref "U3") (pin "TX") (pinfunction "TX_TX") (pintype "bidirectional"))
    )
  )
)
